# Memory_Board_V2.net
KiCad netlist of a schematic drawn in EAGLE
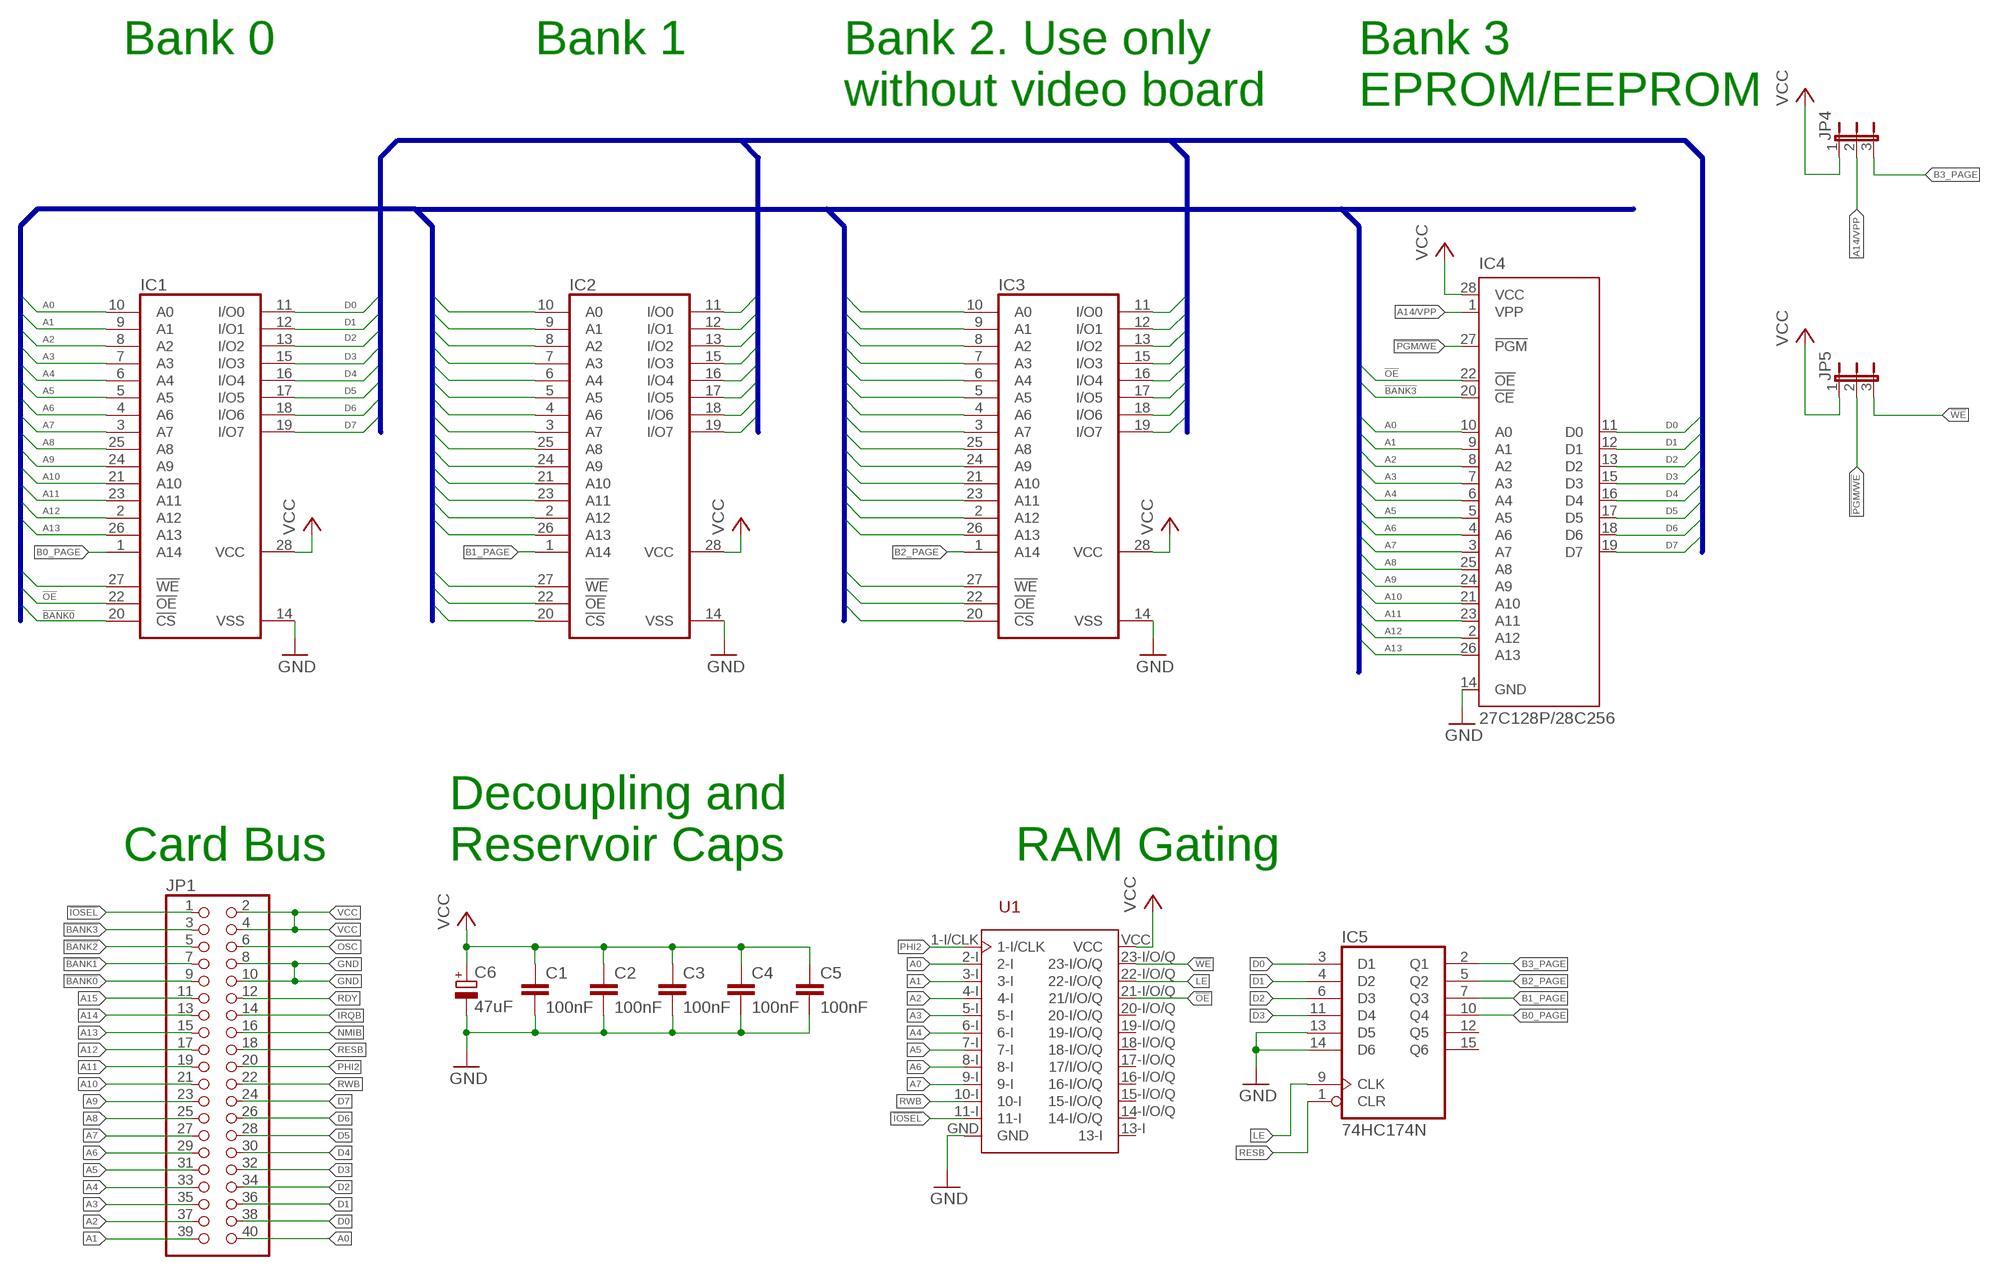
[diagram p0: schematic, sheet 1]

(export (version "E")
  (design (tool "Eeschema 10.0.6"))
  (components
    (comp (ref "C1")
      (value "100nF")
      (footprint "eagle-import:C050-025X075")
      (libsource (lib "eagle-import") (part "C-EU050-025X075"))
    )
    (comp (ref "C2")
      (value "100nF")
      (footprint "eagle-import:C050-025X075")
      (libsource (lib "eagle-import") (part "C-EU050-025X075"))
    )
    (comp (ref "C3")
      (value "100nF")
      (footprint "eagle-import:C050-025X075")
      (libsource (lib "eagle-import") (part "C-EU050-025X075"))
    )
    (comp (ref "C4")
      (value "100nF")
      (footprint "eagle-import:C050-025X075")
      (libsource (lib "eagle-import") (part "C-EU050-025X075"))
    )
    (comp (ref "C5")
      (value "100nF")
      (footprint "eagle-import:C050-025X075")
      (libsource (lib "eagle-import") (part "C-EU050-025X075"))
    )
    (comp (ref "C6")
      (value "47uF")
      (footprint "eagle-import:E2,5-7")
      (libsource (lib "eagle-import") (part "CPOL-EUE2.5-7"))
    )
    (comp (ref "IC1")
      (value "62256P")
      (footprint "eagle-import:DIL28-6")
      (libsource (lib "eagle-import") (part "62256P"))
    )
    (comp (ref "IC2")
      (value "62256P")
      (footprint "eagle-import:DIL28-6")
      (libsource (lib "eagle-import") (part "62256P"))
    )
    (comp (ref "IC3")
      (value "62256P")
      (footprint "eagle-import:DIL28-6")
      (libsource (lib "eagle-import") (part "62256P"))
    )
    (comp (ref "IC4")
      (value "27C128P/28C256")
      (footprint "eagle-import:DIL28-6")
      (libsource (lib "eagle-import") (part "27128PC"))
    )
    (comp (ref "IC5")
      (value "74HC174N")
      (footprint "eagle-import:DIL16")
      (libsource (lib "eagle-import") (part "74174NHC"))
    )
    (comp (ref "JP1")
      (value "PINHD-2X20/90")
      (footprint "eagle-import:2X20_90")
      (libsource (lib "eagle-import") (part "PINHD-2X20/90"))
    )
    (comp (ref "JP4")
      (value "JP2E")
      (footprint "eagle-import:JP2")
      (libsource (lib "eagle-import") (part "JP2E"))
    )
    (comp (ref "JP5")
      (value "JP2E")
      (footprint "eagle-import:JP2")
      (libsource (lib "eagle-import") (part "JP2E"))
    )
    (comp (ref "U1")
      (value "GAL22V10D-DIP")
      (footprint "eagle-import:DIP24")
      (libsource (lib "eagle-import") (part "GAL22V10D-DIP"))
    )
  )
  (nets
    (net (code "1") (name "/~{BANK0}") (class "Default")
      (node (ref "IC1") (pin "20") (pinfunction "~{CS}_20") (pintype "input"))
      (node (ref "JP1") (pin "9") (pinfunction "9_9") (pintype "passive"))
    )
    (net (code "2") (name "/~{BANK1}") (class "Default")
      (node (ref "IC2") (pin "20") (pinfunction "~{CS}_20") (pintype "input"))
      (node (ref "JP1") (pin "7") (pinfunction "7_7") (pintype "passive"))
    )
    (net (code "3") (name "/~{BANK2}") (class "Default")
      (node (ref "IC3") (pin "20") (pinfunction "~{CS}_20") (pintype "input"))
      (node (ref "JP1") (pin "5") (pinfunction "5_5") (pintype "passive"))
    )
    (net (code "4") (name "/~{BANK3}") (class "Default")
      (node (ref "IC4") (pin "20") (pinfunction "~{CE}_20") (pintype "input"))
      (node (ref "JP1") (pin "3") (pinfunction "3_3") (pintype "passive"))
    )
    (net (code "5") (name "/~{IOSEL}") (class "Default")
      (node (ref "JP1") (pin "1") (pinfunction "1_1") (pintype "passive"))
      (node (ref "U1") (pin "11-I") (pinfunction "11-I_11-I") (pintype "input"))
    )
    (net (code "6") (name "/~{OE}") (class "Default")
      (node (ref "IC1") (pin "22") (pinfunction "~{OE}_22") (pintype "input"))
      (node (ref "IC2") (pin "22") (pinfunction "~{OE}_22") (pintype "input"))
      (node (ref "IC3") (pin "22") (pinfunction "~{OE}_22") (pintype "input"))
      (node (ref "IC4") (pin "22") (pinfunction "~{OE}_22") (pintype "input"))
      (node (ref "U1") (pin "21-I/O/Q") (pinfunction "21/I/O/Q_21-I/O/Q") (pintype "bidirectional"))
    )
    (net (code "7") (name "/~{PGM{slash}WE}") (class "Default")
      (node (ref "IC4") (pin "27") (pinfunction "~{PGM}_27") (pintype "passive"))
      (node (ref "JP5") (pin "2") (pinfunction "2_2") (pintype "passive"))
    )
    (net (code "8") (name "/~{WE}") (class "Default")
      (node (ref "IC1") (pin "27") (pinfunction "~{WE}_27") (pintype "input"))
      (node (ref "IC2") (pin "27") (pinfunction "~{WE}_27") (pintype "input"))
      (node (ref "IC3") (pin "27") (pinfunction "~{WE}_27") (pintype "input"))
      (node (ref "JP5") (pin "3") (pinfunction "3_3") (pintype "passive"))
      (node (ref "U1") (pin "23-I/O/Q") (pinfunction "23-I/O/Q_23-I/O/Q") (pintype "bidirectional"))
    )
    (net (code "9") (name "A0") (class "Default")
      (node (ref "IC1") (pin "10") (pinfunction "A0_10") (pintype "input"))
      (node (ref "IC2") (pin "10") (pinfunction "A0_10") (pintype "input"))
      (node (ref "IC3") (pin "10") (pinfunction "A0_10") (pintype "input"))
      (node (ref "IC4") (pin "10") (pinfunction "A0_10") (pintype "input"))
      (node (ref "JP1") (pin "40") (pinfunction "40_40") (pintype "passive"))
      (node (ref "U1") (pin "2-I") (pinfunction "2-I_2-I") (pintype "input"))
    )
    (net (code "10") (name "A1") (class "Default")
      (node (ref "IC1") (pin "9") (pinfunction "A1_9") (pintype "input"))
      (node (ref "IC2") (pin "9") (pinfunction "A1_9") (pintype "input"))
      (node (ref "IC3") (pin "9") (pinfunction "A1_9") (pintype "input"))
      (node (ref "IC4") (pin "9") (pinfunction "A1_9") (pintype "input"))
      (node (ref "JP1") (pin "39") (pinfunction "39_39") (pintype "passive"))
      (node (ref "U1") (pin "3-I") (pinfunction "3-I_3-I") (pintype "input"))
    )
    (net (code "11") (name "A2") (class "Default")
      (node (ref "IC1") (pin "8") (pinfunction "A2_8") (pintype "input"))
      (node (ref "IC2") (pin "8") (pinfunction "A2_8") (pintype "input"))
      (node (ref "IC3") (pin "8") (pinfunction "A2_8") (pintype "input"))
      (node (ref "IC4") (pin "8") (pinfunction "A2_8") (pintype "input"))
      (node (ref "JP1") (pin "37") (pinfunction "37_37") (pintype "passive"))
      (node (ref "U1") (pin "4-I") (pinfunction "4-I_4-I") (pintype "input"))
    )
    (net (code "12") (name "A3") (class "Default")
      (node (ref "IC1") (pin "7") (pinfunction "A3_7") (pintype "input"))
      (node (ref "IC2") (pin "7") (pinfunction "A3_7") (pintype "input"))
      (node (ref "IC3") (pin "7") (pinfunction "A3_7") (pintype "input"))
      (node (ref "IC4") (pin "7") (pinfunction "A3_7") (pintype "input"))
      (node (ref "JP1") (pin "35") (pinfunction "35_35") (pintype "passive"))
      (node (ref "U1") (pin "5-I") (pinfunction "5-I_5-I") (pintype "input"))
    )
    (net (code "13") (name "A4") (class "Default")
      (node (ref "IC1") (pin "6") (pinfunction "A4_6") (pintype "input"))
      (node (ref "IC2") (pin "6") (pinfunction "A4_6") (pintype "input"))
      (node (ref "IC3") (pin "6") (pinfunction "A4_6") (pintype "input"))
      (node (ref "IC4") (pin "6") (pinfunction "A4_6") (pintype "input"))
      (node (ref "JP1") (pin "33") (pinfunction "33_33") (pintype "passive"))
      (node (ref "U1") (pin "6-I") (pinfunction "6-I_6-I") (pintype "input"))
    )
    (net (code "14") (name "A5") (class "Default")
      (node (ref "IC1") (pin "5") (pinfunction "A5_5") (pintype "input"))
      (node (ref "IC2") (pin "5") (pinfunction "A5_5") (pintype "input"))
      (node (ref "IC3") (pin "5") (pinfunction "A5_5") (pintype "input"))
      (node (ref "IC4") (pin "5") (pinfunction "A5_5") (pintype "input"))
      (node (ref "JP1") (pin "31") (pinfunction "31_31") (pintype "passive"))
      (node (ref "U1") (pin "7-I") (pinfunction "7-I_7-I") (pintype "input"))
    )
    (net (code "15") (name "A6") (class "Default")
      (node (ref "IC1") (pin "4") (pinfunction "A6_4") (pintype "input"))
      (node (ref "IC2") (pin "4") (pinfunction "A6_4") (pintype "input"))
      (node (ref "IC3") (pin "4") (pinfunction "A6_4") (pintype "input"))
      (node (ref "IC4") (pin "4") (pinfunction "A6_4") (pintype "input"))
      (node (ref "JP1") (pin "29") (pinfunction "29_29") (pintype "passive"))
      (node (ref "U1") (pin "8-I") (pinfunction "8-I_8-I") (pintype "input"))
    )
    (net (code "16") (name "A7") (class "Default")
      (node (ref "IC1") (pin "3") (pinfunction "A7_3") (pintype "input"))
      (node (ref "IC2") (pin "3") (pinfunction "A7_3") (pintype "input"))
      (node (ref "IC3") (pin "3") (pinfunction "A7_3") (pintype "input"))
      (node (ref "IC4") (pin "3") (pinfunction "A7_3") (pintype "input"))
      (node (ref "JP1") (pin "27") (pinfunction "27_27") (pintype "passive"))
      (node (ref "U1") (pin "9-I") (pinfunction "9-I_9-I") (pintype "input"))
    )
    (net (code "17") (name "A8") (class "Default")
      (node (ref "IC1") (pin "25") (pinfunction "A8_25") (pintype "input"))
      (node (ref "IC2") (pin "25") (pinfunction "A8_25") (pintype "input"))
      (node (ref "IC3") (pin "25") (pinfunction "A8_25") (pintype "input"))
      (node (ref "IC4") (pin "25") (pinfunction "A8_25") (pintype "input"))
      (node (ref "JP1") (pin "25") (pinfunction "25_25") (pintype "passive"))
    )
    (net (code "18") (name "A9") (class "Default")
      (node (ref "IC1") (pin "24") (pinfunction "A9_24") (pintype "input"))
      (node (ref "IC2") (pin "24") (pinfunction "A9_24") (pintype "input"))
      (node (ref "IC3") (pin "24") (pinfunction "A9_24") (pintype "input"))
      (node (ref "IC4") (pin "24") (pinfunction "A9_24") (pintype "input"))
      (node (ref "JP1") (pin "23") (pinfunction "23_23") (pintype "passive"))
    )
    (net (code "19") (name "A10") (class "Default")
      (node (ref "IC1") (pin "21") (pinfunction "A10_21") (pintype "input"))
      (node (ref "IC2") (pin "21") (pinfunction "A10_21") (pintype "input"))
      (node (ref "IC3") (pin "21") (pinfunction "A10_21") (pintype "input"))
      (node (ref "IC4") (pin "21") (pinfunction "A10_21") (pintype "input"))
      (node (ref "JP1") (pin "21") (pinfunction "21_21") (pintype "passive"))
    )
    (net (code "20") (name "A11") (class "Default")
      (node (ref "IC1") (pin "23") (pinfunction "A11_23") (pintype "input"))
      (node (ref "IC2") (pin "23") (pinfunction "A11_23") (pintype "input"))
      (node (ref "IC3") (pin "23") (pinfunction "A11_23") (pintype "input"))
      (node (ref "IC4") (pin "23") (pinfunction "A11_23") (pintype "input"))
      (node (ref "JP1") (pin "19") (pinfunction "19_19") (pintype "passive"))
    )
    (net (code "21") (name "A12") (class "Default")
      (node (ref "IC1") (pin "2") (pinfunction "A12_2") (pintype "input"))
      (node (ref "IC2") (pin "2") (pinfunction "A12_2") (pintype "input"))
      (node (ref "IC3") (pin "2") (pinfunction "A12_2") (pintype "input"))
      (node (ref "IC4") (pin "2") (pinfunction "A12_2") (pintype "input"))
      (node (ref "JP1") (pin "17") (pinfunction "17_17") (pintype "passive"))
    )
    (net (code "22") (name "A13") (class "Default")
      (node (ref "IC1") (pin "26") (pinfunction "A13_26") (pintype "input"))
      (node (ref "IC2") (pin "26") (pinfunction "A13_26") (pintype "input"))
      (node (ref "IC3") (pin "26") (pinfunction "A13_26") (pintype "input"))
      (node (ref "IC4") (pin "26") (pinfunction "A13_26") (pintype "input"))
      (node (ref "JP1") (pin "15") (pinfunction "15_15") (pintype "passive"))
    )
    (net (code "23") (name "A14") (class "Default")
      (node (ref "JP1") (pin "13") (pinfunction "13_13") (pintype "passive"))
    )
    (net (code "24") (name "A14{slash}VPP") (class "Default")
      (node (ref "IC4") (pin "1") (pinfunction "VPP_1") (pintype "input"))
      (node (ref "JP4") (pin "2") (pinfunction "2_2") (pintype "passive"))
    )
    (net (code "25") (name "A15") (class "Default")
      (node (ref "JP1") (pin "11") (pinfunction "11_11") (pintype "passive"))
    )
    (net (code "26") (name "B0_PAGE") (class "Default")
      (node (ref "IC1") (pin "1") (pinfunction "A14_1") (pintype "input"))
      (node (ref "IC5") (pin "10") (pinfunction "Q4_10") (pintype "output"))
    )
    (net (code "27") (name "B1_PAGE") (class "Default")
      (node (ref "IC2") (pin "1") (pinfunction "A14_1") (pintype "input"))
      (node (ref "IC5") (pin "7") (pinfunction "Q3_7") (pintype "output"))
    )
    (net (code "28") (name "B2_PAGE") (class "Default")
      (node (ref "IC3") (pin "1") (pinfunction "A14_1") (pintype "input"))
      (node (ref "IC5") (pin "5") (pinfunction "Q2_5") (pintype "output"))
    )
    (net (code "29") (name "B3_PAGE") (class "Default")
      (node (ref "IC5") (pin "2") (pinfunction "Q1_2") (pintype "output"))
      (node (ref "JP4") (pin "3") (pinfunction "3_3") (pintype "passive"))
    )
    (net (code "30") (name "D0") (class "Default")
      (node (ref "IC1") (pin "11") (pinfunction "I/O0_11") (pintype "bidirectional"))
      (node (ref "IC2") (pin "11") (pinfunction "I/O0_11") (pintype "bidirectional"))
      (node (ref "IC3") (pin "11") (pinfunction "I/O0_11") (pintype "bidirectional"))
      (node (ref "IC4") (pin "11") (pinfunction "D0_11") (pintype "tri_state"))
      (node (ref "IC5") (pin "3") (pinfunction "D1_3") (pintype "input"))
      (node (ref "JP1") (pin "38") (pinfunction "38_38") (pintype "passive"))
    )
    (net (code "31") (name "D1") (class "Default")
      (node (ref "IC1") (pin "12") (pinfunction "I/O1_12") (pintype "bidirectional"))
      (node (ref "IC2") (pin "12") (pinfunction "I/O1_12") (pintype "bidirectional"))
      (node (ref "IC3") (pin "12") (pinfunction "I/O1_12") (pintype "bidirectional"))
      (node (ref "IC4") (pin "12") (pinfunction "D1_12") (pintype "tri_state"))
      (node (ref "IC5") (pin "4") (pinfunction "D2_4") (pintype "input"))
      (node (ref "JP1") (pin "36") (pinfunction "36_36") (pintype "passive"))
    )
    (net (code "32") (name "D2") (class "Default")
      (node (ref "IC1") (pin "13") (pinfunction "I/O2_13") (pintype "bidirectional"))
      (node (ref "IC2") (pin "13") (pinfunction "I/O2_13") (pintype "bidirectional"))
      (node (ref "IC3") (pin "13") (pinfunction "I/O2_13") (pintype "bidirectional"))
      (node (ref "IC4") (pin "13") (pinfunction "D2_13") (pintype "tri_state"))
      (node (ref "IC5") (pin "6") (pinfunction "D3_6") (pintype "input"))
      (node (ref "JP1") (pin "34") (pinfunction "34_34") (pintype "passive"))
    )
    (net (code "33") (name "D3") (class "Default")
      (node (ref "IC1") (pin "15") (pinfunction "I/O3_15") (pintype "bidirectional"))
      (node (ref "IC2") (pin "15") (pinfunction "I/O3_15") (pintype "bidirectional"))
      (node (ref "IC3") (pin "15") (pinfunction "I/O3_15") (pintype "bidirectional"))
      (node (ref "IC4") (pin "15") (pinfunction "D3_15") (pintype "tri_state"))
      (node (ref "IC5") (pin "11") (pinfunction "D4_11") (pintype "input"))
      (node (ref "JP1") (pin "32") (pinfunction "32_32") (pintype "passive"))
    )
    (net (code "34") (name "D4") (class "Default")
      (node (ref "IC1") (pin "16") (pinfunction "I/O4_16") (pintype "bidirectional"))
      (node (ref "IC2") (pin "16") (pinfunction "I/O4_16") (pintype "bidirectional"))
      (node (ref "IC3") (pin "16") (pinfunction "I/O4_16") (pintype "bidirectional"))
      (node (ref "IC4") (pin "16") (pinfunction "D4_16") (pintype "tri_state"))
      (node (ref "JP1") (pin "30") (pinfunction "30_30") (pintype "passive"))
    )
    (net (code "35") (name "D5") (class "Default")
      (node (ref "IC1") (pin "17") (pinfunction "I/O5_17") (pintype "bidirectional"))
      (node (ref "IC2") (pin "17") (pinfunction "I/O5_17") (pintype "bidirectional"))
      (node (ref "IC3") (pin "17") (pinfunction "I/O5_17") (pintype "bidirectional"))
      (node (ref "IC4") (pin "17") (pinfunction "D5_17") (pintype "tri_state"))
      (node (ref "JP1") (pin "28") (pinfunction "28_28") (pintype "passive"))
    )
    (net (code "36") (name "D6") (class "Default")
      (node (ref "IC1") (pin "18") (pinfunction "I/O6_18") (pintype "bidirectional"))
      (node (ref "IC2") (pin "18") (pinfunction "I/O6_18") (pintype "bidirectional"))
      (node (ref "IC3") (pin "18") (pinfunction "I/O6_18") (pintype "bidirectional"))
      (node (ref "IC4") (pin "18") (pinfunction "D6_18") (pintype "tri_state"))
      (node (ref "JP1") (pin "26") (pinfunction "26_26") (pintype "passive"))
    )
    (net (code "37") (name "D7") (class "Default")
      (node (ref "IC1") (pin "19") (pinfunction "I/O7_19") (pintype "bidirectional"))
      (node (ref "IC2") (pin "19") (pinfunction "I/O7_19") (pintype "bidirectional"))
      (node (ref "IC3") (pin "19") (pinfunction "I/O7_19") (pintype "bidirectional"))
      (node (ref "IC4") (pin "19") (pinfunction "D7_19") (pintype "tri_state"))
      (node (ref "JP1") (pin "24") (pinfunction "24_24") (pintype "passive"))
    )
    (net (code "38") (name "GND") (class "Default")
      (node (ref "C1") (pin "2") (pinfunction "2_2") (pintype "passive"))
      (node (ref "C2") (pin "2") (pinfunction "2_2") (pintype "passive"))
      (node (ref "C3") (pin "2") (pinfunction "2_2") (pintype "passive"))
      (node (ref "C4") (pin "2") (pinfunction "2_2") (pintype "passive"))
      (node (ref "C5") (pin "2") (pinfunction "2_2") (pintype "passive"))
      (node (ref "C6") (pin "-") (pinfunction "-_-") (pintype "passive"))
      (node (ref "IC1") (pin "14") (pinfunction "VSS_14") (pintype "power_in"))
      (node (ref "IC2") (pin "14") (pinfunction "VSS_14") (pintype "power_in"))
      (node (ref "IC3") (pin "14") (pinfunction "VSS_14") (pintype "power_in"))
      (node (ref "IC4") (pin "14") (pinfunction "GND_14") (pintype "power_in"))
      (node (ref "IC5") (pin "13") (pinfunction "D5_13") (pintype "input"))
      (node (ref "IC5") (pin "14") (pinfunction "D6_14") (pintype "input"))
      (node (ref "JP1") (pin "10") (pinfunction "10_10") (pintype "passive"))
      (node (ref "JP1") (pin "8") (pinfunction "8_8") (pintype "passive"))
      (node (ref "U1") (pin "GND") (pinfunction "GND_GND") (pintype "power_in"))
    )
    (net (code "39") (name "IRQB") (class "Default")
      (node (ref "JP1") (pin "14") (pinfunction "14_14") (pintype "passive"))
    )
    (net (code "40") (name "LE") (class "Default")
      (node (ref "IC5") (pin "9") (pinfunction "CLK_9") (pintype "input"))
      (node (ref "U1") (pin "22-I/O/Q") (pinfunction "22-I/O/Q_22-I/O/Q") (pintype "bidirectional"))
    )
    (net (code "41") (name "NMIB") (class "Default")
      (node (ref "JP1") (pin "16") (pinfunction "16_16") (pintype "passive"))
    )
    (net (code "42") (name "OSC") (class "Default")
      (node (ref "JP1") (pin "6") (pinfunction "6_6") (pintype "passive"))
    )
    (net (code "43") (name "PHI2") (class "Default")
      (node (ref "JP1") (pin "20") (pinfunction "20_20") (pintype "passive"))
      (node (ref "U1") (pin "1-I/CLK") (pinfunction "1-I/CLK_1-I/CLK") (pintype "input"))
    )
    (net (code "44") (name "RDY") (class "Default")
      (node (ref "JP1") (pin "12") (pinfunction "12_12") (pintype "passive"))
    )
    (net (code "45") (name "RESB") (class "Default")
      (node (ref "IC5") (pin "1") (pinfunction "CLR_1") (pintype "input"))
      (node (ref "JP1") (pin "18") (pinfunction "18_18") (pintype "passive"))
    )
    (net (code "46") (name "RWB") (class "Default")
      (node (ref "JP1") (pin "22") (pinfunction "22_22") (pintype "passive"))
      (node (ref "U1") (pin "10-I") (pinfunction "10-I_10-I") (pintype "input"))
    )
    (net (code "47") (name "VCC") (class "Default")
      (node (ref "C1") (pin "1") (pinfunction "1_1") (pintype "passive"))
      (node (ref "C2") (pin "1") (pinfunction "1_1") (pintype "passive"))
      (node (ref "C3") (pin "1") (pinfunction "1_1") (pintype "passive"))
      (node (ref "C4") (pin "1") (pinfunction "1_1") (pintype "passive"))
      (node (ref "C5") (pin "1") (pinfunction "1_1") (pintype "passive"))
      (node (ref "C6") (pin "+") (pinfunction "+_+") (pintype "passive"))
      (node (ref "IC1") (pin "28") (pinfunction "VCC_28") (pintype "power_in"))
      (node (ref "IC2") (pin "28") (pinfunction "VCC_28") (pintype "power_in"))
      (node (ref "IC3") (pin "28") (pinfunction "VCC_28") (pintype "power_in"))
      (node (ref "IC4") (pin "28") (pinfunction "VCC_28") (pintype "power_in"))
      (node (ref "JP1") (pin "2") (pinfunction "2_2") (pintype "passive"))
      (node (ref "JP1") (pin "4") (pinfunction "4_4") (pintype "passive"))
      (node (ref "JP4") (pin "1") (pinfunction "1_1") (pintype "passive"))
      (node (ref "JP5") (pin "1") (pinfunction "1_1") (pintype "passive"))
      (node (ref "U1") (pin "VCC") (pinfunction "VCC_VCC") (pintype "power_in"))
    )
    (net (code "48") (name "unconnected-(IC5A-Q5-Pad12)") (class "Default")
      (node (ref "IC5") (pin "12") (pinfunction "Q5_12") (pintype "output"))
    )
    (net (code "49") (name "unconnected-(IC5A-Q6-Pad15)") (class "Default")
      (node (ref "IC5") (pin "15") (pinfunction "Q6_15") (pintype "output"))
    )
    (net (code "50") (name "unconnected-(U1-17{slash}I{slash}O{slash}Q-Pad17-I{slash}O{slash}Q)") (class "Default")
      (node (ref "U1") (pin "17-I/O/Q") (pinfunction "17/I/O/Q_17-I/O/Q") (pintype "bidirectional"))
    )
    (net (code "51") (name "unconnected-(U1-Pad13-I)") (class "Default")
      (node (ref "U1") (pin "13-I") (pinfunction "13-I_13-I") (pintype "input"))
    )
    (net (code "52") (name "unconnected-(U1-Pad14-I{slash}O{slash}Q)") (class "Default")
      (node (ref "U1") (pin "14-I/O/Q") (pinfunction "14-I/O/Q_14-I/O/Q") (pintype "bidirectional"))
    )
    (net (code "53") (name "unconnected-(U1-Pad15-I{slash}O{slash}Q)") (class "Default")
      (node (ref "U1") (pin "15-I/O/Q") (pinfunction "15-I/O/Q_15-I/O/Q") (pintype "bidirectional"))
    )
    (net (code "54") (name "unconnected-(U1-Pad16-I{slash}O{slash}Q)") (class "Default")
      (node (ref "U1") (pin "16-I/O/Q") (pinfunction "16-I/O/Q_16-I/O/Q") (pintype "bidirectional"))
    )
    (net (code "55") (name "unconnected-(U1-Pad18-I{slash}O{slash}Q)") (class "Default")
      (node (ref "U1") (pin "18-I/O/Q") (pinfunction "18-I/O/Q_18-I/O/Q") (pintype "bidirectional"))
    )
    (net (code "56") (name "unconnected-(U1-Pad19-I{slash}O{slash}Q)") (class "Default")
      (node (ref "U1") (pin "19-I/O/Q") (pinfunction "19-I/O/Q_19-I/O/Q") (pintype "bidirectional"))
    )
    (net (code "57") (name "unconnected-(U1-Pad20-I{slash}O{slash}Q)") (class "Default")
      (node (ref "U1") (pin "20-I/O/Q") (pinfunction "20-I/O/Q_20-I/O/Q") (pintype "bidirectional"))
    )
  )
)
